# SCH_Business-Card_2025-07-10.net
KiCad netlist of a schematic drawn in EasyEDA
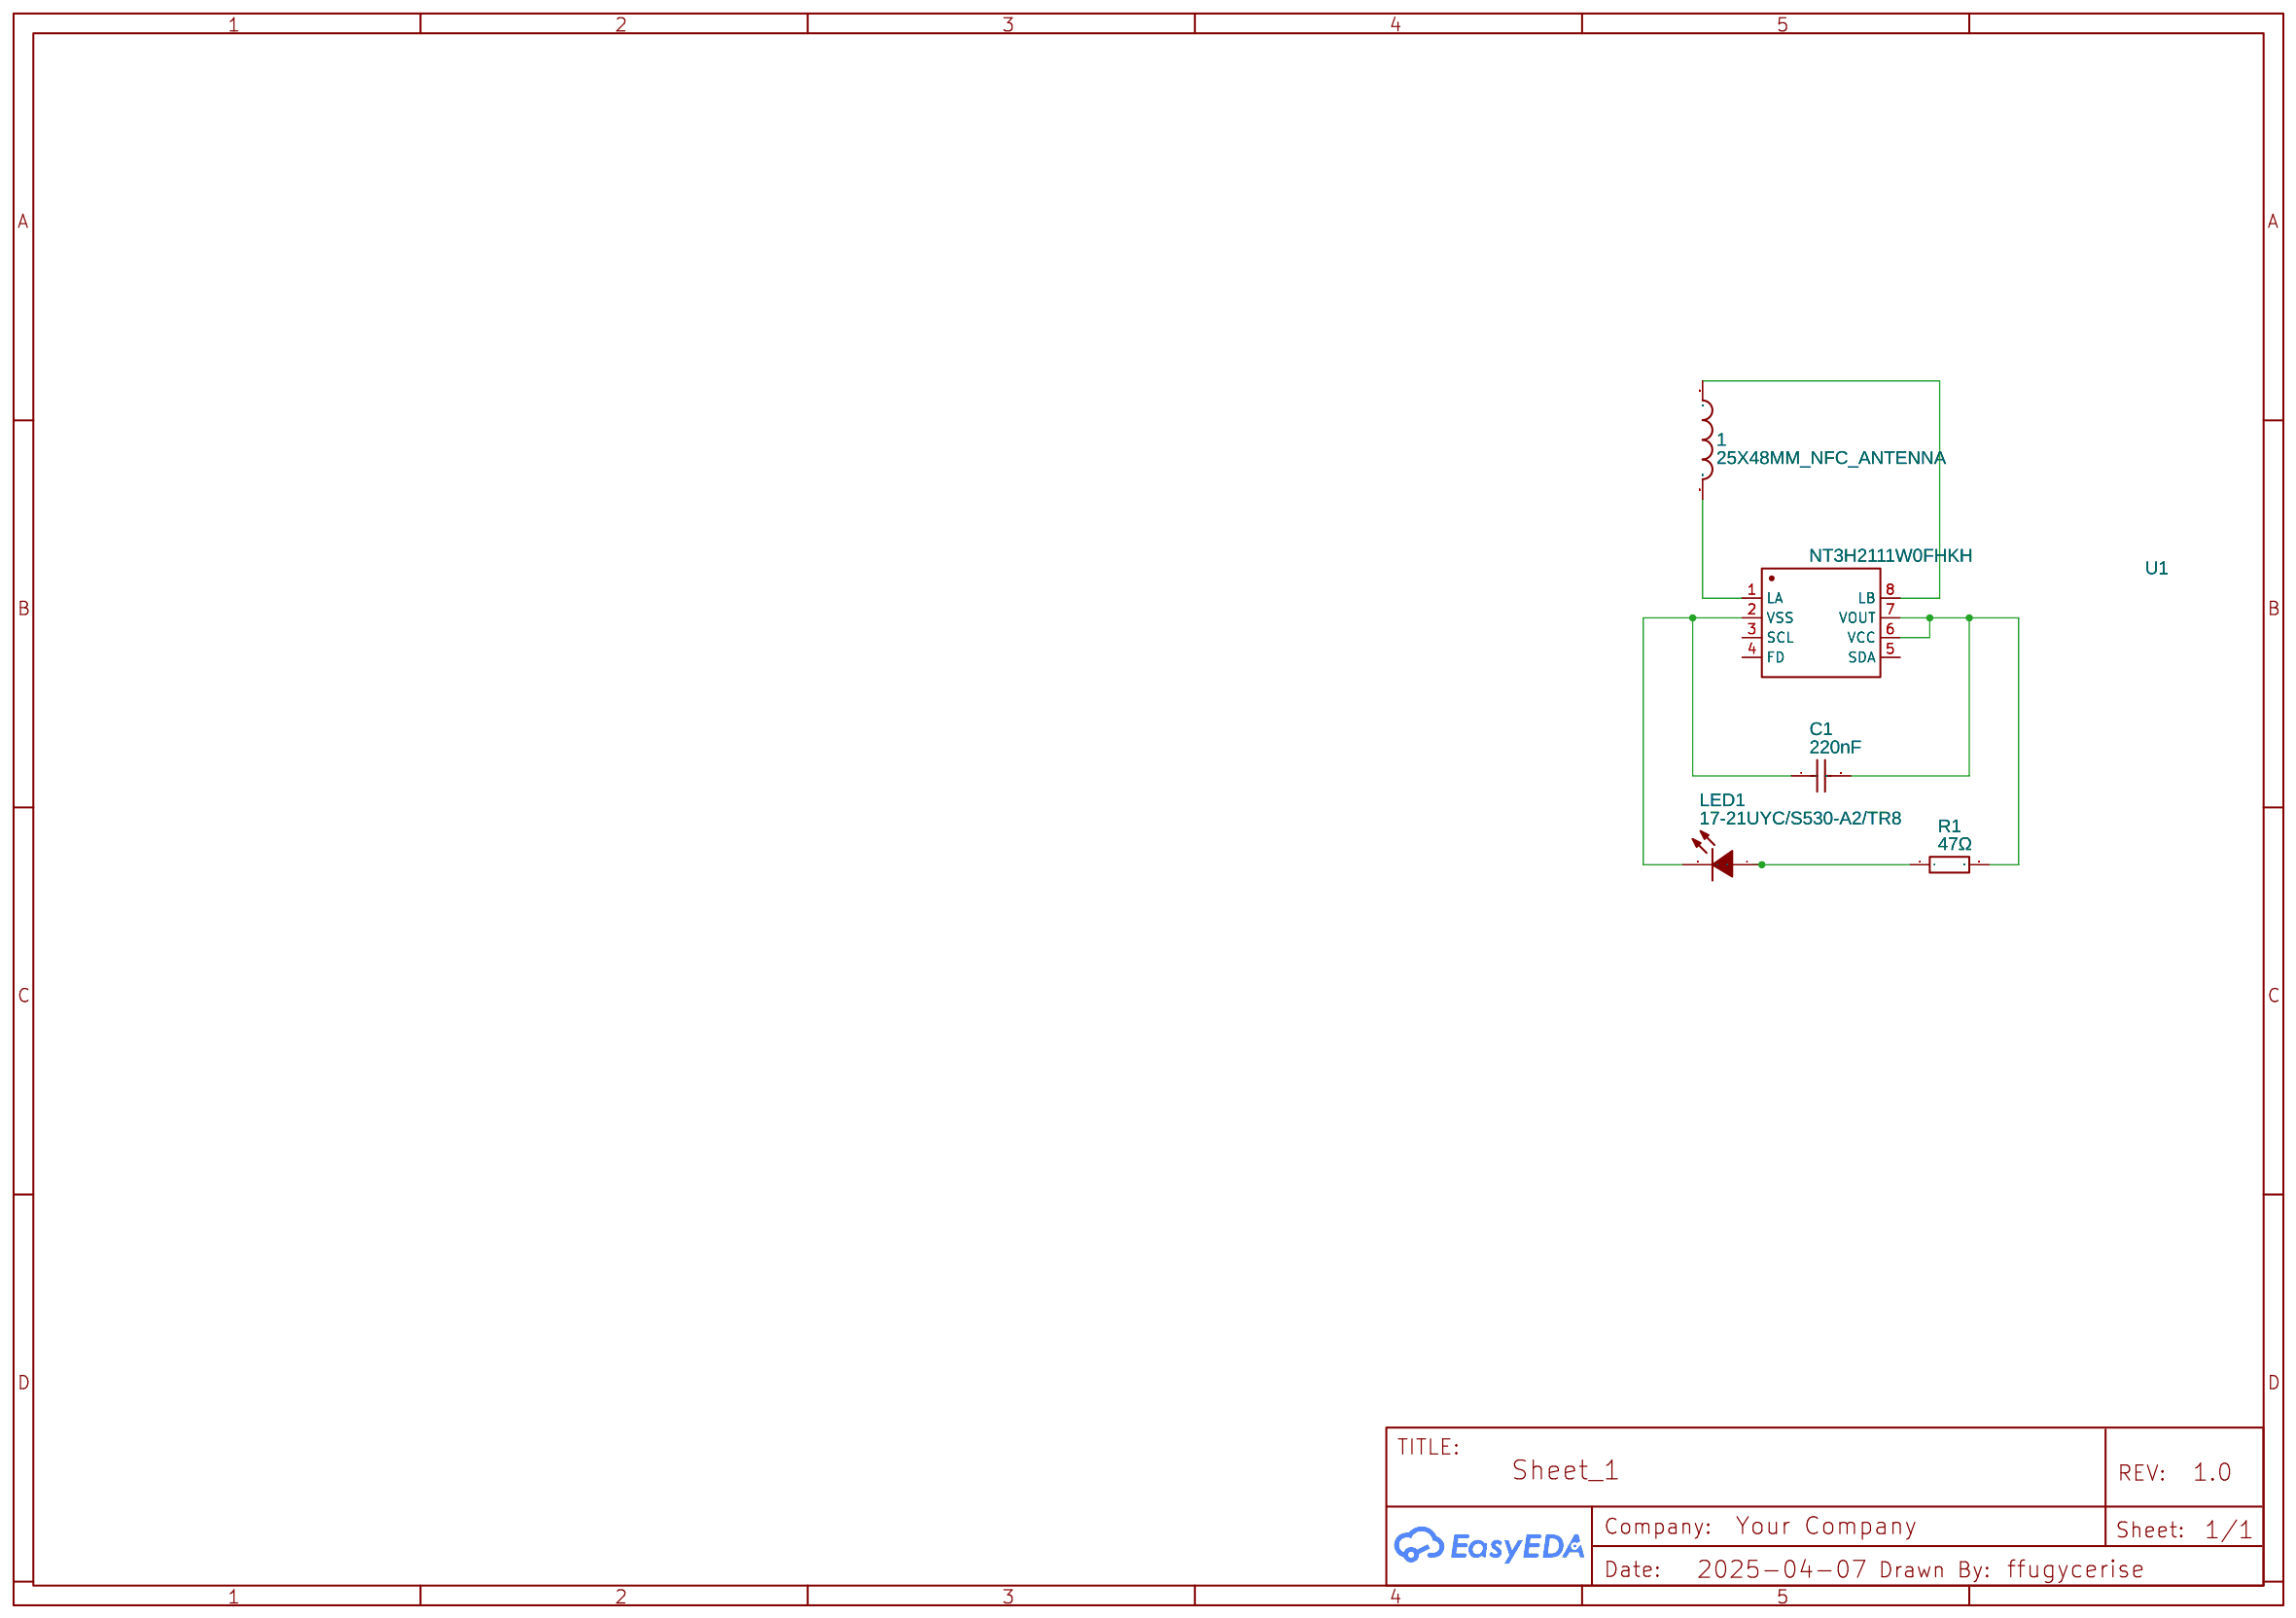
[diagram p0: schematic sheet]

(export (version "E")
  (design (tool "Eeschema 10.0.6"))
  (components
    (comp (ref "1") (value "25X48MM_NFC_ANTENNA") (libsource (lib "") (part "25X48MM_NFC_ANTENNA")))
    (comp (ref "C1")
      (value "220nF")
      (fields
        (field (name "Manufacturer Part") "CL10B224KA8NNNC")
        (field (name "Manufacturer") "SAMSUNG(三星)")
      )
      (libsource (lib "") (part "CL10B224KA8NNNC"))
    )
    (comp (ref "LED1")
      (value "17-21UYC/S530-A2/TR8")
      (fields (field (name "Manufacturer") "EVERLIGHT(亿光)"))
      (libsource (lib "") (part "17-21UYC/S530-A2/TR8"))
    )
    (comp (ref "R1")
      (value "47Ω")
      (fields
        (field (name "Manufacturer Part") "0603WAF470JT5E")
        (field (name "Manufacturer") "UNI-ROYAL(厚声)")
      )
      (libsource (lib "") (part "0603WAF470JT5E"))
    )
    (comp (ref "U1")
      (value "NT3H2111W0FHKH")
      (fields (field (name "Manufacturer") "NXP(恩智浦)"))
      (libsource (lib "") (part "NT3H2111W0FHKH"))
    )
  )
  (nets
    (net (code "1") (name "Net-(LED1-+)") (class "Default")
      (node (ref "LED1") (pin "1") (pinfunction "+_1") (pintype "unspecified"))
      (node (ref "R1") (pin "1") (pinfunction "1_1") (pintype "input"))
    )
    (net (code "2") (name "Net-(LED1--)") (class "Default")
      (node (ref "C1") (pin "1") (pinfunction "1_1") (pintype "input"))
      (node (ref "LED1") (pin "2") (pinfunction "-_2") (pintype "unspecified"))
      (node (ref "U1") (pin "2") (pinfunction "VSS_2") (pintype "unspecified"))
    )
    (net (code "3") (name "Net-(U1-LA)") (class "Default")
      (node (ref "1") (pin "P$2") (pinfunction "P$2_P$2") (pintype "bidirectional"))
      (node (ref "U1") (pin "1") (pinfunction "LA_1") (pintype "unspecified"))
    )
    (net (code "4") (name "Net-(U1-LB)") (class "Default")
      (node (ref "1") (pin "P$1") (pinfunction "P$1_P$1") (pintype "bidirectional"))
      (node (ref "U1") (pin "8") (pinfunction "LB_8") (pintype "unspecified"))
    )
    (net (code "5") (name "Net-(U1-VCC)") (class "Default")
      (node (ref "C1") (pin "2") (pinfunction "2_2") (pintype "input"))
      (node (ref "R1") (pin "2") (pinfunction "2_2") (pintype "input"))
      (node (ref "U1") (pin "6") (pinfunction "VCC_6") (pintype "unspecified"))
      (node (ref "U1") (pin "7") (pinfunction "VOUT_7") (pintype "unspecified"))
    )
    (net (code "6") (name "unconnected-(U1-FD-Pad4)") (class "Default")
      (node (ref "U1") (pin "4") (pinfunction "FD_4") (pintype "unspecified"))
    )
    (net (code "7") (name "unconnected-(U1-SCL-Pad3)") (class "Default")
      (node (ref "U1") (pin "3") (pinfunction "SCL_3") (pintype "unspecified"))
    )
    (net (code "8") (name "unconnected-(U1-SDA-Pad5)") (class "Default")
      (node (ref "U1") (pin "5") (pinfunction "SDA_5") (pintype "unspecified"))
    )
  )
)
